# untitled.net
KiCad netlist of a schematic drawn in EAGLE
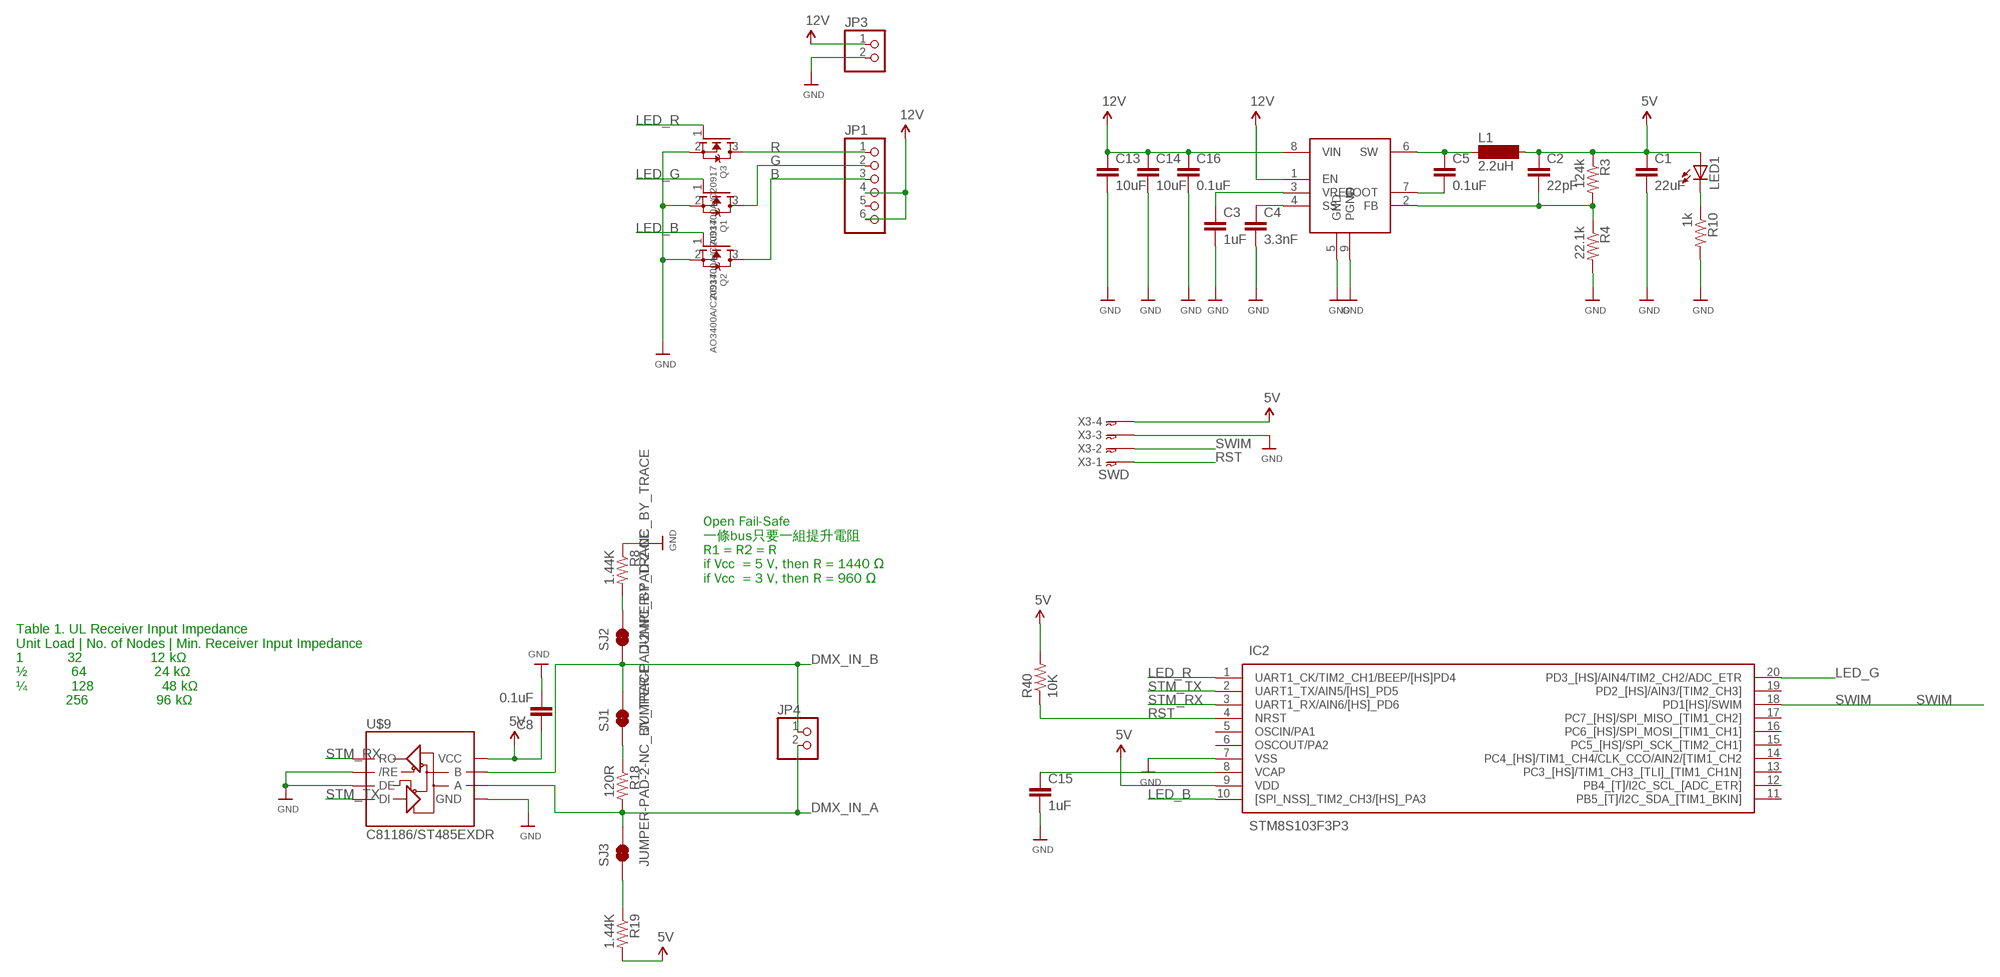
[diagram p0: schematic, sheet 1]

(export (version "E")
  (design (tool "Eeschema 10.0.6"))
  (components
    (comp (ref "C1")
      (value "22uF")
      (footprint "eagle-import:0805-CAP")
      (libsource (lib "eagle-import") (part "CAPACITOR-0805"))
    )
    (comp (ref "C2")
      (value "22pF")
      (footprint "eagle-import:0805-CAP")
      (libsource (lib "eagle-import") (part "CAPACITOR-0805"))
    )
    (comp (ref "C3")
      (value "1uF")
      (footprint "eagle-import:0603-CAP")
      (libsource (lib "eagle-import") (part "CAPACITOR-0603"))
    )
    (comp (ref "C4")
      (value "3.3nF")
      (footprint "eagle-import:0603-CAP")
      (libsource (lib "eagle-import") (part "CAPACITOR-0603"))
    )
    (comp (ref "C5")
      (value "0.1uF")
      (footprint "eagle-import:0603-CAP")
      (libsource (lib "eagle-import") (part "CAPACITOR-0603"))
    )
    (comp (ref "C8")
      (value "0.1uF")
      (footprint "eagle-import:0402-CAP")
      (libsource (lib "eagle-import") (part "CAPACITOR-0402"))
    )
    (comp (ref "C13")
      (value "10uF")
      (footprint "eagle-import:0603-CAP")
      (libsource (lib "eagle-import") (part "CAPACITOR-0603"))
    )
    (comp (ref "C14")
      (value "10uF")
      (footprint "eagle-import:0603-CAP")
      (libsource (lib "eagle-import") (part "CAPACITOR-0603"))
    )
    (comp (ref "C15")
      (value "1uF")
      (footprint "eagle-import:0603-CAP")
      (libsource (lib "eagle-import") (part "CAPACITOR-0603"))
    )
    (comp (ref "C16")
      (value "0.1uF")
      (footprint "eagle-import:0603-CAP")
      (libsource (lib "eagle-import") (part "CAPACITOR-0603"))
    )
    (comp (ref "IC2")
      (value "STM8S103F3P3")
      (footprint "eagle-import:SOP65P640X120-20N")
      (fields (field (name "MOUSER_PART_NUMBER") "511-STM8S103F3P3"))
      (libsource (lib "eagle-import") (part "STM8S103F3P3"))
    )
    (comp (ref "JP1")
      (value "HEADER-1X6")
      (footprint "eagle-import:1X06_OVAL")
      (libsource (lib "eagle-import") (part "HEADER-1X6"))
    )
    (comp (ref "JP3")
      (value "HEADER-1X2")
      (footprint "eagle-import:1X02_OVAL")
      (libsource (lib "eagle-import") (part "HEADER-1X2"))
    )
    (comp (ref "JP4")
      (value "HEADER-1X2")
      (footprint "eagle-import:1X02_OVAL")
      (libsource (lib "eagle-import") (part "HEADER-1X2"))
    )
    (comp (ref "L1")
      (value "2.2uH")
      (footprint "eagle-import:MS2.5X20")
      (libsource (lib "eagle-import") (part "MS502.5X2"))
    )
    (comp (ref "LED1")
      (value "LEDCHIPLED_0603")
      (footprint "eagle-import:CHIPLED_0603")
      (libsource (lib "eagle-import") (part "LEDCHIPLED_0603"))
    )
    (comp (ref "Q1")
      (value "AO3400A/C20917")
      (footprint "eagle-import:SOT23")
      (libsource (lib "eagle-import") (part "MOSFET-NREFLOW"))
    )
    (comp (ref "Q2")
      (value "AO3400A/C20917")
      (footprint "eagle-import:SOT23")
      (libsource (lib "eagle-import") (part "MOSFET-NREFLOW"))
    )
    (comp (ref "Q3")
      (value "AO3400A/C20917")
      (footprint "eagle-import:SOT23")
      (libsource (lib "eagle-import") (part "MOSFET-NREFLOW"))
    )
    (comp (ref "R3")
      (value "124k")
      (footprint "eagle-import:R0603")
      (libsource (lib "eagle-import") (part "R-US_R0603"))
    )
    (comp (ref "R4")
      (value "22.1k")
      (footprint "eagle-import:R0603")
      (libsource (lib "eagle-import") (part "R-US_R0603"))
    )
    (comp (ref "R8")
      (value "1.44K")
      (footprint "eagle-import:R0603")
      (libsource (lib "eagle-import") (part "R-US_R0603"))
    )
    (comp (ref "R10")
      (value "1k")
      (footprint "eagle-import:R0603")
      (libsource (lib "eagle-import") (part "R-US_R0603"))
    )
    (comp (ref "R18")
      (value "120R")
      (footprint "eagle-import:R0603")
      (libsource (lib "eagle-import") (part "R-US_R0603"))
    )
    (comp (ref "R19")
      (value "1.44K")
      (footprint "eagle-import:R0603")
      (libsource (lib "eagle-import") (part "R-US_R0603"))
    )
    (comp (ref "R40")
      (value "10K")
      (footprint "eagle-import:R0402")
      (libsource (lib "eagle-import") (part "R-US_R0402"))
    )
    (comp (ref "SJ1")
      (value "JUMPER-PAD-2-NC_BY_TRACE")
      (footprint "eagle-import:PAD-JUMPER-2-NC_BY_TRACE_YES_SILK")
      (libsource (lib "eagle-import") (part "JUMPER-PAD-2-NC_BY_TRACE"))
    )
    (comp (ref "SJ2")
      (value "JUMPER-PAD-2-NC_BY_TRACE")
      (footprint "eagle-import:PAD-JUMPER-2-NC_BY_TRACE_YES_SILK")
      (libsource (lib "eagle-import") (part "JUMPER-PAD-2-NC_BY_TRACE"))
    )
    (comp (ref "SJ3")
      (value "JUMPER-PAD-2-NC_BY_TRACE")
      (footprint "eagle-import:PAD-JUMPER-2-NC_BY_TRACE_YES_SILK")
      (libsource (lib "eagle-import") (part "JUMPER-PAD-2-NC_BY_TRACE"))
    )
    (comp (ref "U$1")
      (value "RT7240GSP")
      (footprint "eagle-import:SO08-THERMALPAD")
      (libsource (lib "eagle-import") (part "RT7240GSP"))
    )
    (comp (ref "U$9")
      (value "C81186/ST485EXDR")
      (footprint "eagle-import:SO08")
      (libsource (lib "eagle-import") (part "RS485SOIC"))
    )
    (comp (ref "X3")
      (value "SWD")
      (footprint "eagle-import:B4B-XH")
      (libsource (lib "eagle-import") (part "04-JST-B4B-XH-A"))
    )
  )
  (nets
    (net (code "1") (name "/B") (class "Default")
      (node (ref "JP1") (pin "3") (pinfunction "3_3") (pintype "passive"))
      (node (ref "Q2") (pin "3") (pinfunction "D_3") (pintype "bidirectional"))
    )
    (net (code "2") (name "/DMX_IN_A") (class "Default")
      (node (ref "JP4") (pin "2") (pinfunction "2_2") (pintype "passive"))
      (node (ref "R18") (pin "2") (pinfunction "2_2") (pintype "passive"))
      (node (ref "SJ3") (pin "2") (pinfunction "2_2") (pintype "passive"))
      (node (ref "U$9") (pin "6") (pinfunction "A_6") (pintype "bidirectional"))
    )
    (net (code "3") (name "/DMX_IN_B") (class "Default")
      (node (ref "JP4") (pin "1") (pinfunction "1_1") (pintype "passive"))
      (node (ref "SJ1") (pin "2") (pinfunction "2_2") (pintype "passive"))
      (node (ref "SJ2") (pin "1") (pinfunction "1_1") (pintype "passive"))
      (node (ref "U$9") (pin "7") (pinfunction "B_7") (pintype "bidirectional"))
    )
    (net (code "4") (name "/G") (class "Default")
      (node (ref "JP1") (pin "2") (pinfunction "2_2") (pintype "passive"))
      (node (ref "Q1") (pin "3") (pinfunction "D_3") (pintype "bidirectional"))
    )
    (net (code "5") (name "/LED_B") (class "Default")
      (node (ref "IC2") (pin "10") (pinfunction "[SPI_NSS]_TIM2_CH3/[HS]_PA3_10") (pintype "bidirectional"))
      (node (ref "Q2") (pin "1") (pinfunction "G_1") (pintype "bidirectional"))
    )
    (net (code "6") (name "/LED_G") (class "Default")
      (node (ref "IC2") (pin "20") (pinfunction "PD3_[HS]/AIN4/TIM2_CH2/ADC_ETR_20") (pintype "input"))
      (node (ref "Q1") (pin "1") (pinfunction "G_1") (pintype "bidirectional"))
    )
    (net (code "7") (name "/LED_R") (class "Default")
      (node (ref "IC2") (pin "1") (pinfunction "UART1_CK/TIM2_CH1/BEEP/[HS]PD4_1") (pintype "bidirectional"))
      (node (ref "Q3") (pin "1") (pinfunction "G_1") (pintype "bidirectional"))
    )
    (net (code "8") (name "/R") (class "Default")
      (node (ref "JP1") (pin "1") (pinfunction "1_1") (pintype "passive"))
      (node (ref "Q3") (pin "3") (pinfunction "D_3") (pintype "bidirectional"))
    )
    (net (code "9") (name "/RST") (class "Default")
      (node (ref "IC2") (pin "4") (pinfunction "NRST_4") (pintype "input"))
      (node (ref "R40") (pin "1") (pinfunction "1_1") (pintype "passive"))
      (node (ref "X3") (pin "P$1") (pinfunction "1_P$1") (pintype "passive"))
    )
    (net (code "10") (name "/STM_RX") (class "Default")
      (node (ref "IC2") (pin "3") (pinfunction "UART1_RX/AIN6/[HS]_PD6_3") (pintype "input"))
      (node (ref "U$9") (pin "1") (pinfunction "RO_1") (pintype "bidirectional"))
    )
    (net (code "11") (name "/STM_TX") (class "Default")
      (node (ref "IC2") (pin "2") (pinfunction "UART1_TX/AIN5/[HS]_PD5_2") (pintype "input"))
      (node (ref "U$9") (pin "4") (pinfunction "DI_4") (pintype "bidirectional"))
    )
    (net (code "12") (name "/SWIM") (class "Default")
      (node (ref "IC2") (pin "18") (pinfunction "PD1[HS]/SWIM_18") (pintype "bidirectional"))
      (node (ref "X3") (pin "P$2") (pinfunction "1_P$2") (pintype "passive"))
    )
    (net (code "13") (name "5V") (class "Default")
      (node (ref "C1") (pin "P$1") (pinfunction "1_P$1") (pintype "passive"))
      (node (ref "C2") (pin "P$1") (pinfunction "1_P$1") (pintype "passive"))
      (node (ref "C8") (pin "P$1") (pinfunction "1_P$1") (pintype "passive"))
      (node (ref "IC2") (pin "9") (pinfunction "VDD_9") (pintype "power_in"))
      (node (ref "L1") (pin "2") (pinfunction "2_2") (pintype "passive"))
      (node (ref "LED1") (pin "A") (pinfunction "A_A") (pintype "passive"))
      (node (ref "R19") (pin "2") (pinfunction "2_2") (pintype "passive"))
      (node (ref "R3") (pin "1") (pinfunction "1_1") (pintype "passive"))
      (node (ref "R40") (pin "2") (pinfunction "2_2") (pintype "passive"))
      (node (ref "U$9") (pin "8") (pinfunction "VCC_8") (pintype "bidirectional"))
      (node (ref "X3") (pin "P$4") (pinfunction "1_P$4") (pintype "passive"))
    )
    (net (code "14") (name "12V") (class "Default")
      (node (ref "C13") (pin "P$1") (pinfunction "1_P$1") (pintype "passive"))
      (node (ref "C14") (pin "P$1") (pinfunction "1_P$1") (pintype "passive"))
      (node (ref "C16") (pin "P$1") (pinfunction "1_P$1") (pintype "passive"))
      (node (ref "JP1") (pin "4") (pinfunction "4_4") (pintype "passive"))
      (node (ref "JP1") (pin "6") (pinfunction "6_6") (pintype "passive"))
      (node (ref "JP3") (pin "1") (pinfunction "1_1") (pintype "passive"))
      (node (ref "U$1") (pin "1") (pinfunction "EN_1") (pintype "bidirectional"))
      (node (ref "U$1") (pin "8") (pinfunction "VIN_8") (pintype "bidirectional"))
    )
    (net (code "15") (name "GND") (class "Default")
      (node (ref "C1") (pin "P$2") (pinfunction "2_P$2") (pintype "passive"))
      (node (ref "C13") (pin "P$2") (pinfunction "2_P$2") (pintype "passive"))
      (node (ref "C14") (pin "P$2") (pinfunction "2_P$2") (pintype "passive"))
      (node (ref "C15") (pin "P$2") (pinfunction "2_P$2") (pintype "passive"))
      (node (ref "C16") (pin "P$2") (pinfunction "2_P$2") (pintype "passive"))
      (node (ref "C3") (pin "P$2") (pinfunction "2_P$2") (pintype "passive"))
      (node (ref "C4") (pin "P$2") (pinfunction "2_P$2") (pintype "passive"))
      (node (ref "C8") (pin "P$2") (pinfunction "2_P$2") (pintype "passive"))
      (node (ref "IC2") (pin "7") (pinfunction "VSS_7") (pintype "power_in"))
      (node (ref "JP3") (pin "2") (pinfunction "2_2") (pintype "passive"))
      (node (ref "Q1") (pin "2") (pinfunction "S_2") (pintype "bidirectional"))
      (node (ref "Q2") (pin "2") (pinfunction "S_2") (pintype "bidirectional"))
      (node (ref "Q3") (pin "2") (pinfunction "S_2") (pintype "bidirectional"))
      (node (ref "R10") (pin "2") (pinfunction "2_2") (pintype "passive"))
      (node (ref "R4") (pin "2") (pinfunction "2_2") (pintype "passive"))
      (node (ref "R8") (pin "1") (pinfunction "1_1") (pintype "passive"))
      (node (ref "U$1") (pin "5") (pinfunction "GND_5") (pintype "bidirectional"))
      (node (ref "U$1") (pin "9") (pinfunction "PGND_9") (pintype "bidirectional"))
      (node (ref "U$9") (pin "2") (pinfunction "/RE_2") (pintype "bidirectional"))
      (node (ref "U$9") (pin "3") (pinfunction "DE_3") (pintype "bidirectional"))
      (node (ref "U$9") (pin "5") (pinfunction "GND_5") (pintype "bidirectional"))
      (node (ref "X3") (pin "P$3") (pinfunction "1_P$3") (pintype "passive"))
    )
    (net (code "16") (name "Net-(C2-2)") (class "Default")
      (node (ref "C2") (pin "P$2") (pinfunction "2_P$2") (pintype "passive"))
      (node (ref "R3") (pin "2") (pinfunction "2_2") (pintype "passive"))
      (node (ref "R4") (pin "1") (pinfunction "1_1") (pintype "passive"))
      (node (ref "U$1") (pin "2") (pinfunction "FB_2") (pintype "bidirectional"))
    )
    (net (code "17") (name "Net-(C3-1)") (class "Default")
      (node (ref "C3") (pin "P$1") (pinfunction "1_P$1") (pintype "passive"))
      (node (ref "U$1") (pin "3") (pinfunction "VREG_3") (pintype "bidirectional"))
    )
    (net (code "18") (name "Net-(C4-1)") (class "Default")
      (node (ref "C4") (pin "P$1") (pinfunction "1_P$1") (pintype "passive"))
      (node (ref "U$1") (pin "4") (pinfunction "SS_4") (pintype "bidirectional"))
    )
    (net (code "19") (name "Net-(C5-1)") (class "Default")
      (node (ref "C5") (pin "P$1") (pinfunction "1_P$1") (pintype "passive"))
      (node (ref "L1") (pin "1") (pinfunction "1_1") (pintype "passive"))
      (node (ref "U$1") (pin "6") (pinfunction "SW_6") (pintype "bidirectional"))
    )
    (net (code "20") (name "Net-(C5-2)") (class "Default")
      (node (ref "C5") (pin "P$2") (pinfunction "2_P$2") (pintype "passive"))
      (node (ref "U$1") (pin "7") (pinfunction "BOOT_7") (pintype "bidirectional"))
    )
    (net (code "21") (name "Net-(C15-1)") (class "Default")
      (node (ref "C15") (pin "P$1") (pinfunction "1_P$1") (pintype "passive"))
      (node (ref "IC2") (pin "8") (pinfunction "VCAP_8") (pintype "bidirectional"))
    )
    (net (code "22") (name "Net-(LED1-PadC)") (class "Default")
      (node (ref "LED1") (pin "C") (pinfunction "C_C") (pintype "passive"))
      (node (ref "R10") (pin "1") (pinfunction "1_1") (pintype "passive"))
    )
    (net (code "23") (name "Net-(R8-Pad2)") (class "Default")
      (node (ref "R8") (pin "2") (pinfunction "2_2") (pintype "passive"))
      (node (ref "SJ2") (pin "2") (pinfunction "2_2") (pintype "passive"))
    )
    (net (code "24") (name "Net-(R18-Pad1)") (class "Default")
      (node (ref "R18") (pin "1") (pinfunction "1_1") (pintype "passive"))
      (node (ref "SJ1") (pin "1") (pinfunction "1_1") (pintype "passive"))
    )
    (net (code "25") (name "Net-(R19-Pad1)") (class "Default")
      (node (ref "R19") (pin "1") (pinfunction "1_1") (pintype "passive"))
      (node (ref "SJ3") (pin "1") (pinfunction "1_1") (pintype "passive"))
    )
    (net (code "26") (name "unconnected-(IC2-OSCIN{slash}PA1-Pad5)") (class "Default")
      (node (ref "IC2") (pin "5") (pinfunction "OSCIN/PA1_5") (pintype "input"))
    )
    (net (code "27") (name "unconnected-(IC2-OSCOUT{slash}PA2-Pad6)") (class "Default")
      (node (ref "IC2") (pin "6") (pinfunction "OSCOUT/PA2_6") (pintype "output"))
    )
    (net (code "28") (name "unconnected-(IC2-PB4_[T]{slash}I2C_SCL_[ADC_ETR]-Pad12)") (class "Default")
      (node (ref "IC2") (pin "12") (pinfunction "PB4_[T]/I2C_SCL_[ADC_ETR]_12") (pintype "bidirectional"))
    )
    (net (code "29") (name "unconnected-(IC2-PB5_[T]{slash}I2C_SDA_[TIM1_BKIN]-Pad11)") (class "Default")
      (node (ref "IC2") (pin "11") (pinfunction "PB5_[T]/I2C_SDA_[TIM1_BKIN]_11") (pintype "input"))
    )
    (net (code "30") (name "unconnected-(IC2-PC3_[HS]{slash}TIM1_CH3_[TLI]_[TIM1_CH1N]-Pad13)") (class "Default")
      (node (ref "IC2") (pin "13") (pinfunction "PC3_[HS]/TIM1_CH3_[TLI]_[TIM1_CH1N]_13") (pintype "bidirectional"))
    )
    (net (code "31") (name "unconnected-(IC2-PC4_[HS]{slash}TIM1_CH4{slash}CLK_CCO{slash}AIN2{slash}[TIM1_CH2-Pad14)") (class "Default")
      (node (ref "IC2") (pin "14") (pinfunction "PC4_[HS]/TIM1_CH4/CLK_CCO/AIN2/[TIM1_CH2_14") (pintype "input"))
    )
    (net (code "32") (name "unconnected-(IC2-PC5_[HS]{slash}SPI_SCK_[TIM2_CH1]-Pad15)") (class "Default")
      (node (ref "IC2") (pin "15") (pinfunction "PC5_[HS]/SPI_SCK_[TIM2_CH1]_15") (pintype "bidirectional"))
    )
    (net (code "33") (name "unconnected-(IC2-PC6_[HS]{slash}SPI_MOSI_[TIM1_CH1]-Pad16)") (class "Default")
      (node (ref "IC2") (pin "16") (pinfunction "PC6_[HS]/SPI_MOSI_[TIM1_CH1]_16") (pintype "bidirectional"))
    )
    (net (code "34") (name "unconnected-(IC2-PC7_[HS]{slash}SPI_MISO_[TIM1_CH2]-Pad17)") (class "Default")
      (node (ref "IC2") (pin "17") (pinfunction "PC7_[HS]/SPI_MISO_[TIM1_CH2]_17") (pintype "bidirectional"))
    )
    (net (code "35") (name "unconnected-(IC2-PD2_[HS]{slash}AIN3{slash}[TIM2_CH3]-Pad19)") (class "Default")
      (node (ref "IC2") (pin "19") (pinfunction "PD2_[HS]/AIN3/[TIM2_CH3]_19") (pintype "input"))
    )
    (net (code "36") (name "unconnected-(JP1-Pad5)") (class "Default")
      (node (ref "JP1") (pin "5") (pinfunction "5_5") (pintype "passive"))
    )
  )
)
